# shinobi_3v_3V3_dcdc_jack.net
KiCad netlist of a schematic drawn in EAGLE
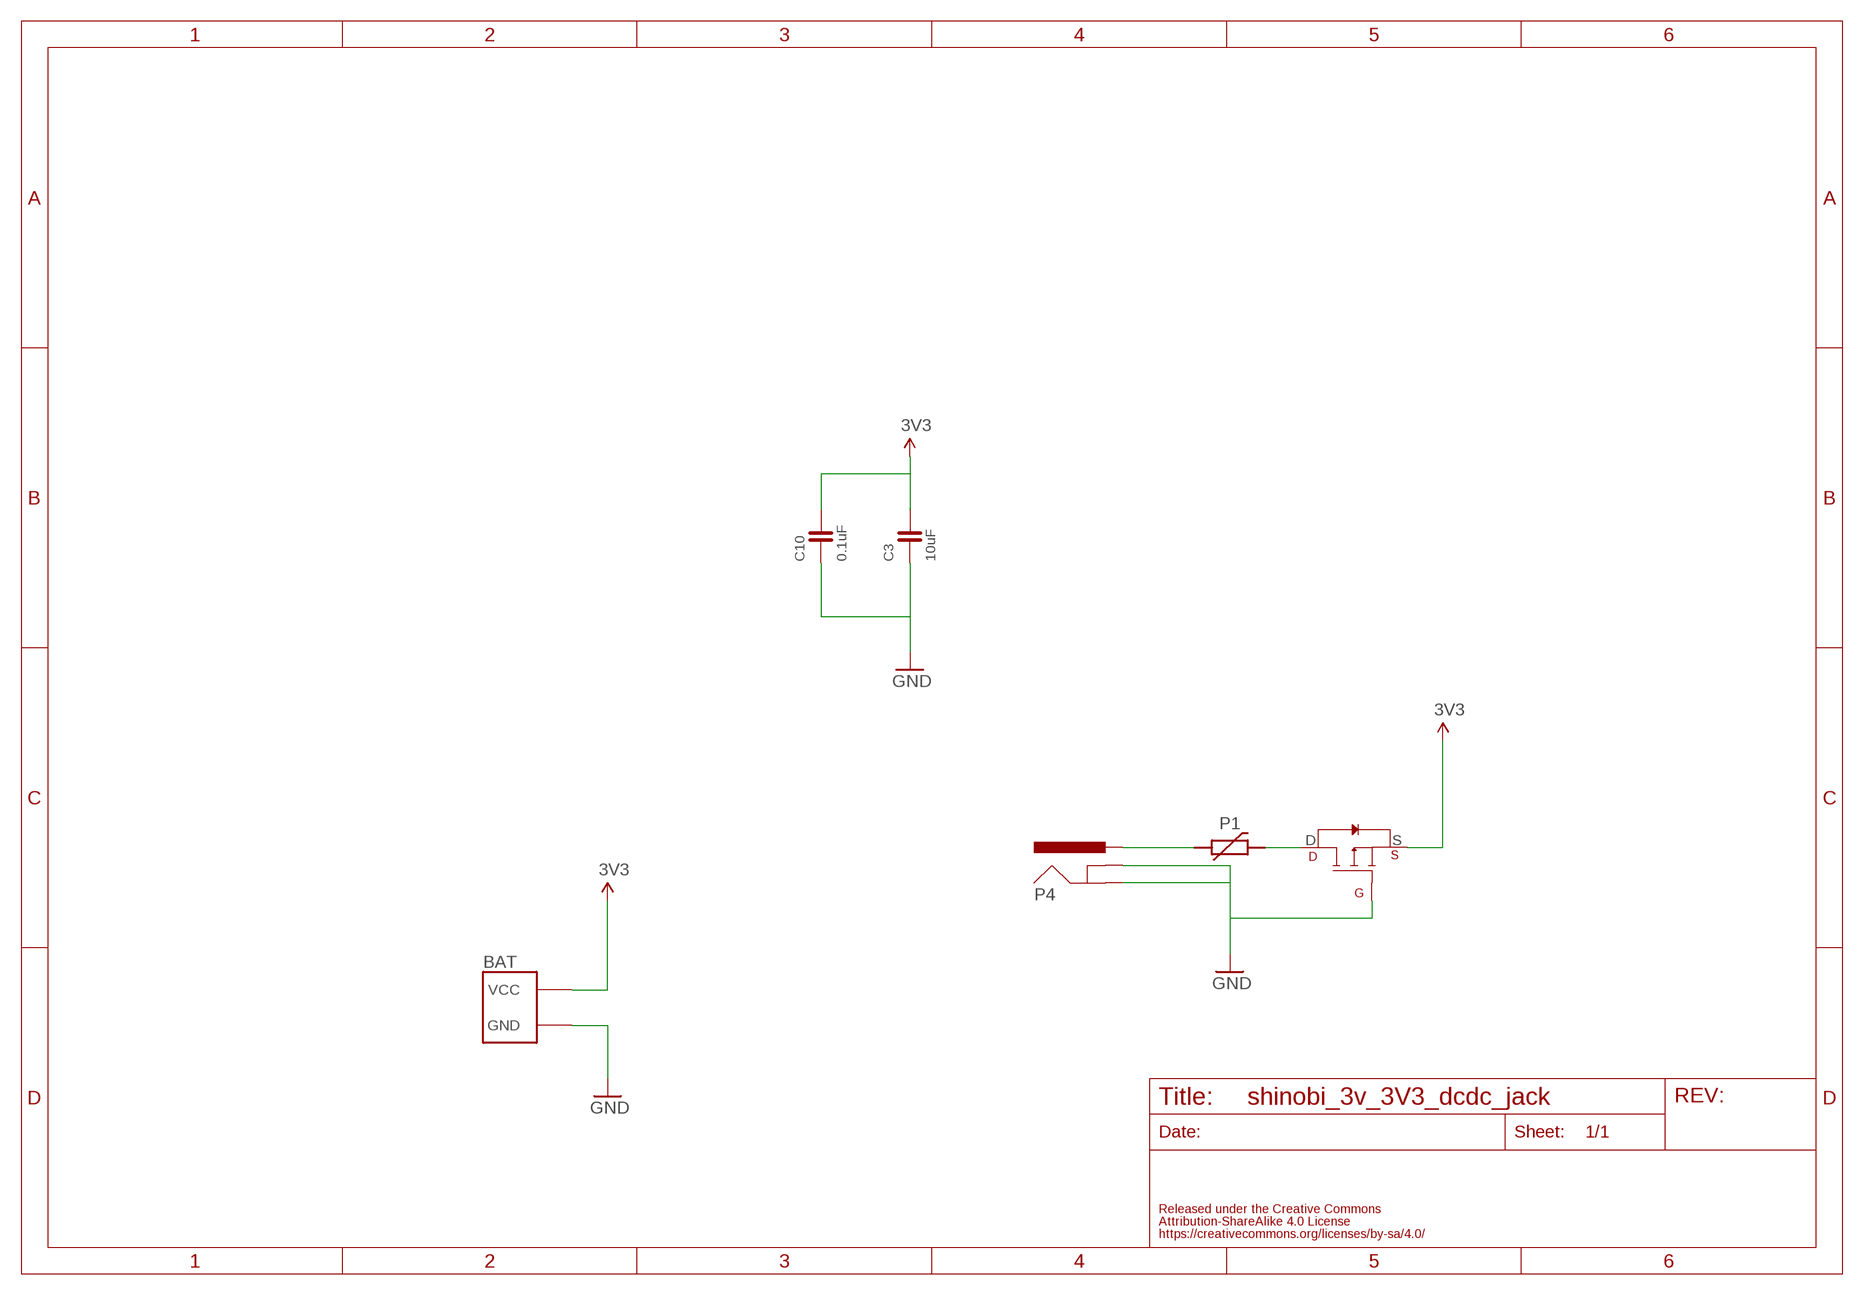
[diagram p0: schematic, sheet 1]

(export (version "E")
  (design (tool "Eeschema 10.0.6"))
  (components
    (comp (ref "BAT")
      (value "FABO_BRICK_2PIN_SIDE")
      (footprint "eagle-import:FABO_BRICK_2PIN_S02B−PASK-2_SILK")
      (libsource (lib "eagle-import") (part "FABO_BRICK_2PIN_SIDE"))
    )
    (comp (ref "C3")
      (value "10uF")
      (footprint "eagle-import:0603")
      (libsource (lib "eagle-import") (part "CAPACITOR-0603"))
    )
    (comp (ref "C10")
      (value "0.1uF")
      (footprint "eagle-import:0603")
      (libsource (lib "eagle-import") (part "CAPACITOR-0603"))
    )
    (comp (ref "M1")
      (value "AOD417")
      (footprint "eagle-import:AOD417")
      (libsource (lib "eagle-import") (part "AOD417"))
    )
    (comp (ref "P1")
      (value "POLYSWITCH1210")
      (footprint "eagle-import:1210")
      (libsource (lib "eagle-import") (part "POLYSWITCH1210"))
    )
    (comp (ref "P4")
      (value "DC-JACKMA04339A0")
      (footprint "eagle-import:M04339A0")
      (libsource (lib "eagle-import") (part "DC-JACKMA04339A0"))
    )
  )
  (nets
    (net (code "1") (name "3V3") (class "Default")
      (node (ref "BAT") (pin "VCC") (pinfunction "VCC_VCC") (pintype "bidirectional"))
      (node (ref "C10") (pin "2") (pinfunction "2_2") (pintype "passive"))
      (node (ref "C3") (pin "2") (pinfunction "2_2") (pintype "passive"))
      (node (ref "M1") (pin "S") (pinfunction "S_S") (pintype "bidirectional"))
    )
    (net (code "2") (name "GND") (class "Default")
      (node (ref "BAT") (pin "GND") (pinfunction "GND_GND") (pintype "bidirectional"))
      (node (ref "C10") (pin "1") (pinfunction "1_1") (pintype "passive"))
      (node (ref "C3") (pin "1") (pinfunction "1_1") (pintype "passive"))
      (node (ref "M1") (pin "G") (pinfunction "G_G") (pintype "bidirectional"))
      (node (ref "P4") (pin "GND@2") (pinfunction "GND_GND@2") (pintype "bidirectional"))
      (node (ref "P4") (pin "GND@3") (pinfunction "GNDBREAK_GND@3") (pintype "bidirectional"))
    )
    (net (code "3") (name "Net-(P1-1)") (class "Default")
      (node (ref "P1") (pin "P$1") (pinfunction "1_P$1") (pintype "bidirectional"))
      (node (ref "P4") (pin "VCC") (pinfunction "PWR_VCC") (pintype "bidirectional"))
    )
    (net (code "4") (name "Net-(P1-2)") (class "Default")
      (node (ref "M1") (pin "D") (pinfunction "D_D") (pintype "bidirectional"))
      (node (ref "P1") (pin "P$2") (pinfunction "2_P$2") (pintype "bidirectional"))
    )
  )
)
